# PLC_dual_power_input.net
KiCad netlist of a schematic drawn in Altium Designer
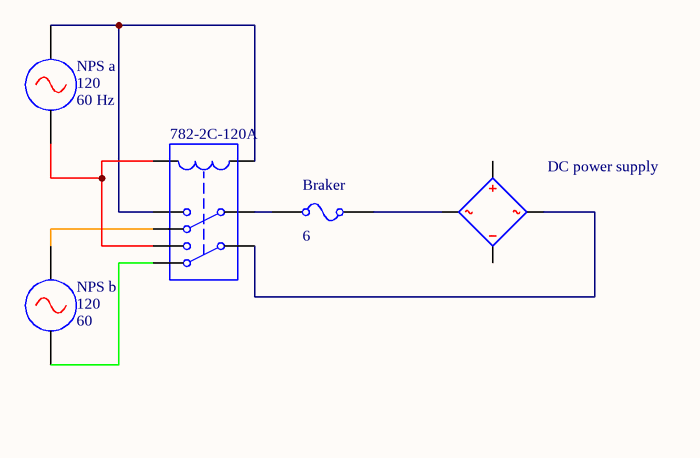
[diagram p0: PLC dual power input.SchDoc]

(export (version "E")
  (design (tool "Eeschema 10.0.6"))
  (components
    (comp (ref "782-2C-120A")
      (value "Double-Pole, Double-Throw Relay")
      (libsource (lib "Simulation Generic Components") (part "DPDT Relay"))
    )
    (comp (ref "Braker")
      (value "Fuse")
      (fields (field (name "CURRENT") "6"))
      (libsource (lib "Simulation Generic Components") (part "Fuse"))
    )
    (comp (ref "DC power supply")
      (value "Four Diodes Bridge Rectifier")
      (libsource (lib "Simulation Generic Components") (part "Bridge Rectifier"))
    )
    (comp (ref "NPS a")
      (value "AC Voltage Source")
      (fields (field (name "V") "120") (field (name "FREQ") "60 Hz"))
      (libsource (lib "Simulation Generic Components") (part "AC Voltage Source"))
    )
    (comp (ref "NPS b")
      (value "AC Voltage Source")
      (fields (field (name "VOLTAGE") "120") (field (name "FREQ") "60"))
      (libsource (lib "Simulation Generic Components") (part "AC Voltage Source"))
    )
  )
  (nets
    (net (code "1") (name "Net-(782-2C-120A-Pad1)") (class "Default")
      (node (ref "782-2C-120A") (pin "1") (pinfunction "1_1") (pintype "passive"))
      (node (ref "DC power supply") (pin "2") (pinfunction "2_2") (pintype "passive"))
    )
    (net (code "2") (name "Net-(782-2C-120A-Pad2)") (class "Default")
      (node (ref "782-2C-120A") (pin "2") (pinfunction "2_2") (pintype "passive"))
      (node (ref "782-2C-120A") (pin "8") (pinfunction "8_8") (pintype "passive"))
      (node (ref "NPS a") (pin "2") (pinfunction "2_2") (pintype "passive"))
    )
    (net (code "3") (name "Net-(782-2C-120A-Pad3)") (class "Default")
      (node (ref "782-2C-120A") (pin "3") (pinfunction "3_3") (pintype "passive"))
      (node (ref "NPS b") (pin "2") (pinfunction "2_2") (pintype "passive"))
    )
    (net (code "4") (name "Net-(782-2C-120A-Pad4)") (class "Default")
      (node (ref "782-2C-120A") (pin "4") (pinfunction "4_4") (pintype "passive"))
      (node (ref "Braker") (pin "1") (pinfunction "1_1") (pintype "passive"))
    )
    (net (code "5") (name "Net-(782-2C-120A-Pad5)") (class "Default")
      (node (ref "782-2C-120A") (pin "5") (pinfunction "5_5") (pintype "passive"))
      (node (ref "782-2C-120A") (pin "7") (pinfunction "7_7") (pintype "passive"))
      (node (ref "NPS a") (pin "1") (pinfunction "1_1") (pintype "passive"))
    )
    (net (code "6") (name "Net-(782-2C-120A-Pad6)") (class "Default")
      (node (ref "782-2C-120A") (pin "6") (pinfunction "6_6") (pintype "passive"))
      (node (ref "NPS b") (pin "1") (pinfunction "1_1") (pintype "passive"))
    )
    (net (code "7") (name "Net-(Braker-Pad2)") (class "Default")
      (node (ref "Braker") (pin "2") (pinfunction "2_2") (pintype "passive"))
      (node (ref "DC power supply") (pin "1") (pinfunction "1_1") (pintype "passive"))
    )
    (net (code "8") (name "unconnected-(DC power supply-NEG-Pad4)") (class "Default")
      (node (ref "DC power supply") (pin "4") (pinfunction "NEG_4") (pintype "passive"))
    )
    (net (code "9") (name "unconnected-(DC power supply-POS-Pad3)") (class "Default")
      (node (ref "DC power supply") (pin "3") (pinfunction "POS_3") (pintype "passive"))
    )
  )
)
